# PCB_Project.net
KiCad netlist of a schematic drawn in Altium Designer
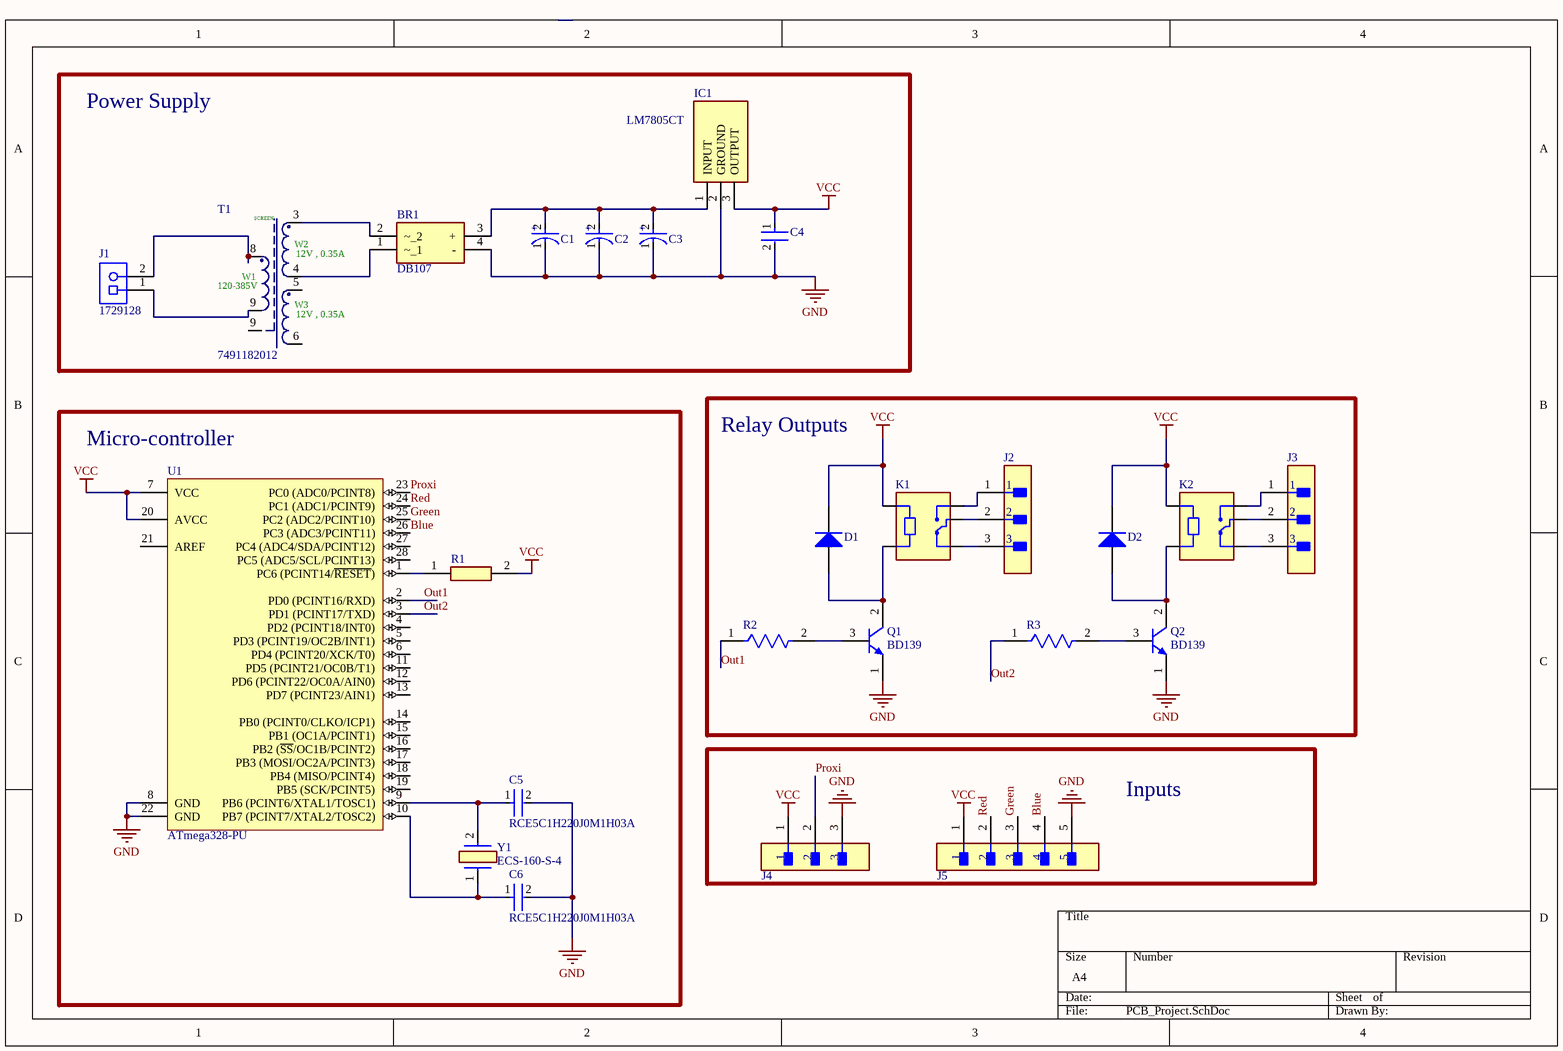
[diagram p0: PCB_Project.SchDoc]

(export (version "E")
  (design (tool "Eeschema 10.0.6"))
  (components
    (comp (ref "BR1")
      (value "DB107")
      (footprint "SamacSys:DIP825W50P510L830H340Q4N")
      (description "Bridge Rectifier")
      (fields (field (name "MOUSER PART NUMBER") "583-DB107"))
      (libsource (lib "*") (part "DB107"))
    )
    (comp (ref "C1")
      (value "EEUTA1E101")
      (footprint "FP-RAD-TH-D_8_0_5-L_11_5-MFG")
      (description "Aluminum Electrolytic Capacitors (Radial Lead Type) AEC-Q200 Qualified 100uF ±20% 25V")
      (fields (field (name "VOLTAGE") "25V") (field (name "TOLERANCE") "20%"))
      (libsource (lib "Altium Content Vault") (part "203bc49f2ac43e59fd269a8c329ed05"))
    )
    (comp (ref "C2")
      (value "ECA2CHG470B")
      (footprint "FP-RAD-TH-D_12_5_0_5-L_20-MFG")
      (description "Aluminum Electrolytic Capacitors (Radial Lead Type) 47uF ±20% 160V")
      (fields (field (name "TOLERANCE") "20%"))
      (libsource (lib "Altium Content Vault") (part "a00bbbee19879c290e62620ae7e47b1"))
    )
    (comp (ref "C3")
      (value "ECA2AM100")
      (footprint "FP-RAD-TH-D_5_0_5-L_11_1-MFG")
      (description "Aluminum Electrolytic Capacitors (Radial Lead Type) 10uF ±20% 100V")
      (fields (field (name "VOLTAGE") "100V") (field (name "TOLERANCE") "20%"))
      (libsource (lib "Altium Content Vault") (part "a00bbbee19879c290e62620ae7e47b1"))
    )
    (comp (ref "C4")
      (value "RCER72A104K1K1H03B")
      (footprint "FP-RCE1K1-2_5-MFG")
      (description "Cap Ceramic Monolithic 100nF 100V 10% Thru-Hole Bulk")
      (fields (field (name "TOLERANCE") "10%"))
      (libsource (lib "Altium Content Vault") (part "02cd4be3c70576c341d710602a673aa"))
    )
    (comp (ref "C5")
      (value "RCE5C1H220J0M1H03A")
      (footprint "FP-RCE0K1-MFG")
      (description "Cap Ceramic 22pF 50V C0G ±5% Radial 5mm +125°C Automotive Bulk")
      (fields (field (name "TOLERANCE") "5%"))
      (libsource (lib "Altium Content Vault") (part "b4654b650e69147ec39a6b967a45e02"))
    )
    (comp (ref "C6")
      (value "RCE5C1H220J0M1H03A")
      (footprint "FP-RCE0K1-MFG")
      (description "Cap Ceramic 22pF 50V C0G ±5% Radial 5mm +125°C Automotive Bulk")
      (fields (field (name "TOLERANCE") "5%"))
      (libsource (lib "Altium Content Vault") (part "b4654b650e69147ec39a6b967a45e02"))
    )
    (comp (ref "D1")
      (value "1N4001-T")
      (footprint "DIOD-DO-41-P-2_V")
      (description "1.0 A Rectifier, 15 pF, 50 V, -65 to 150 degC, 2-Pin DO-41 Plastic, RoHS, Tape and Reel")
      (fields (field (name "MANUFACTURER") "Diodes Inc"))
      (libsource (lib "Altium Content Vault") (part "DIOD-D-A1K2-2"))
    )
    (comp (ref "D2")
      (value "1N4001-T")
      (footprint "DIOD-DO-41-P-2_V")
      (description "1.0 A Rectifier, 15 pF, 50 V, -65 to 150 degC, 2-Pin DO-41 Plastic, RoHS, Tape and Reel")
      (fields (field (name "MANUFACTURER") "Diodes Inc"))
      (libsource (lib "Altium Content Vault") (part "DIOD-D-A1K2-2"))
    )
    (comp (ref "IC1")
      (value "LM7805CT")
      (footprint "SamacSys:TO254P470X1028X1955-3P")
      (description "Integrated Circuit")
      (fields (field (name "MOUSER PART NUMBER") "926-LM7805CT"))
      (libsource (lib "*") (part "LM7805CT"))
    )
    (comp (ref "J1")
      (value "1729128")
      (footprint "PHOE-1729128-2_V")
      (description "PCB Terminal Block, 13.5 A, 400 V, 2-Pin THD, RoHS, Bulk")
      (fields (field (name "MANUFACTURER") "Phoenix Contact"))
      (libsource (lib "Altium Content Vault") (part "CN-2P-F-R2"))
    )
    (comp (ref "J2")
      (value "B3B-XH-A(LF)(SN)")
      (footprint "FP-B3B-XH-A_LF_SN-MFG")
      (description "CONN HEADER VERT 3POS 2.5MM")
      (libsource (lib "Altium Content Vault") (part "0d3f023dd272f625e17a2be33dea85f"))
    )
    (comp (ref "J3")
      (value "B3B-XH-A(LF)(SN)")
      (footprint "FP-B3B-XH-A_LF_SN-MFG")
      (description "CONN HEADER VERT 3POS 2.5MM")
      (libsource (lib "Altium Content Vault") (part "0d3f023dd272f625e17a2be33dea85f"))
    )
    (comp (ref "J4")
      (value "B3B-XH-A(LF)(SN)")
      (footprint "FP-B3B-XH-A_LF_SN-MFG")
      (description "CONN HEADER VERT 3POS 2.5MM")
      (libsource (lib "") (part "0d3f023dd272f625e17a2be33dea85f_1"))
    )
    (comp (ref "J5")
      (value "B5B-EH-A(LF)(SN)")
      (footprint "FP-B5B-EH-A_LF_SN-MFG")
      (description "CONN HEADER VERT 5POS 2.5MM")
      (libsource (lib "Altium Content Vault") (part "bf93c07fd2649a848d0ec8585582aab"))
    )
    (comp (ref "K1")
      (value "SRD-05VDC-SL-C")
      (footprint "RELAY_SRD-05VDC-SL-C")
      (fields (field (name "MF") "Songle Relay"))
      (libsource (lib "SRD-05VDC-SL-C") (part "SRD-05VDC-SL-C"))
    )
    (comp (ref "K2")
      (value "SRD-05VDC-SL-C")
      (footprint "RELAY_SRD-05VDC-SL-C")
      (fields (field (name "MF") "Songle Relay"))
      (libsource (lib "SRD-05VDC-SL-C") (part "SRD-05VDC-SL-C"))
    )
    (comp (ref "Q1")
      (value "BD139")
      (footprint "ONSC-TO-225-3-77-09")
      (description "Plastic Medium-Power Silicon NPN Transistor, 3-Pin TO-225, Bulk Box")
      (fields (field (name "MANUFACTURER") "On Semiconductor"))
      (libsource (lib "Altium Content Vault") (part "ONSC-NPN-E1C2B3-3"))
    )
    (comp (ref "Q2")
      (value "BD139")
      (footprint "ONSC-TO-225-3-77-09")
      (description "Plastic Medium-Power Silicon NPN Transistor, 3-Pin TO-225, Bulk Box")
      (fields (field (name "MANUFACTURER") "On Semiconductor"))
      (libsource (lib "Altium Content Vault") (part "ONSC-NPN-E1C2B3-3"))
    )
    (comp (ref "R1")
      (value "PR02000201001JR500")
      (footprint "SamacSys:RESAD2760W63L1200D390")
      (description "Resistor")
      (fields (field (name "MOUSER PART NUMBER") "594-5083NW1K000J"))
      (libsource (lib "*") (part "PR02000201001JR500"))
    )
    (comp (ref "R2")
      (value "MFR-25FBF52-1K18")
      (footprint "FP-MFR-25-MFG")
      (description "1.18 kOhms ±1% 0.25W, 1/4W Through Hole Resistor Axial  Metal Film")
      (fields (field (name "MANUFACTURER") "Yageo"))
      (libsource (lib "Altium Content Vault") (part "1029c3af85768c4190bb7ad29bc67b5"))
    )
    (comp (ref "R3")
      (value "MFR-25FBF52-1K18")
      (footprint "FP-MFR-25-MFG")
      (description "1.18 kOhms ±1% 0.25W, 1/4W Through Hole Resistor Axial  Metal Film")
      (fields (field (name "MANUFACTURER") "Yageo"))
      (libsource (lib "Altium Content Vault") (part "1029c3af85768c4190bb7ad29bc67b5"))
    )
    (comp (ref "T1")
      (value "7491182012")
      (footprint "EE16_7_4 (E16)")
      (description "Off-Line Transformer WE-UNIT , L=0.9mH")
      (fields (field (name "MANUFACTURER") "Wuerth Elektronik"))
      (libsource (lib "Altium Content Vault") (part "WE-7491182012"))
    )
    (comp (ref "U1")
      (value "ATmega328-PU")
      (footprint "28P3")
      (libsource (lib "Altium Content Vault") (part "MC-8B-ATM48-IL28"))
    )
    (comp (ref "Y1")
      (value "ECS-160-S-4")
      (footprint "SamacSys:ECS160S4")
      (description "Crystal or Oscillator")
      (fields (field (name "MOUSER PART NUMBER") "520-HCU1600-S"))
      (libsource (lib "*") (part "ECS-160-S-4"))
    )
  )
  (nets
    (net (code "1") (name "/Blue") (class "Default")
      (node (ref "J5") (pin "4") (pinfunction "4_4") (pintype "passive"))
      (node (ref "U1") (pin "26") (pinfunction "PC3_(ADC3/PCINT11)_26") (pintype "bidirectional"))
    )
    (net (code "2") (name "/Green") (class "Default")
      (node (ref "J5") (pin "3") (pinfunction "3_3") (pintype "passive"))
      (node (ref "U1") (pin "25") (pinfunction "PC2_(ADC2/PCINT10)_25") (pintype "bidirectional"))
    )
    (net (code "3") (name "/Out1") (class "Default")
      (node (ref "R2") (pin "1") (pinfunction "1_1") (pintype "passive"))
      (node (ref "U1") (pin "2") (pinfunction "PD0_(PCINT16/RXD)_2") (pintype "bidirectional"))
    )
    (net (code "4") (name "/Out2") (class "Default")
      (node (ref "R3") (pin "1") (pinfunction "1_1") (pintype "passive"))
      (node (ref "U1") (pin "3") (pinfunction "PD1_(PCINT17/TXD)_3") (pintype "bidirectional"))
    )
    (net (code "5") (name "/Proxi") (class "Default")
      (node (ref "J4") (pin "2") (pinfunction "2_2") (pintype "passive"))
      (node (ref "U1") (pin "23") (pinfunction "PC0_(ADC0/PCINT8)_23") (pintype "bidirectional"))
    )
    (net (code "6") (name "/Red") (class "Default")
      (node (ref "J5") (pin "2") (pinfunction "2_2") (pintype "passive"))
      (node (ref "U1") (pin "24") (pinfunction "PC1_(ADC1/PCINT9)_24") (pintype "bidirectional"))
    )
    (net (code "7") (name "GND") (class "Default")
      (node (ref "BR1") (pin "4") (pinfunction "-_4") (pintype "passive"))
      (node (ref "C1") (pin "1") (pinfunction "C_1") (pintype "passive"))
      (node (ref "C2") (pin "1") (pinfunction "C_1") (pintype "passive"))
      (node (ref "C3") (pin "1") (pinfunction "C_1") (pintype "passive"))
      (node (ref "C4") (pin "2") (pinfunction "2_2") (pintype "passive"))
      (node (ref "C5") (pin "2") (pinfunction "2_2") (pintype "passive"))
      (node (ref "C6") (pin "2") (pinfunction "2_2") (pintype "passive"))
      (node (ref "IC1") (pin "2") (pinfunction "GROUND_2") (pintype "passive"))
      (node (ref "J4") (pin "3") (pinfunction "3_3") (pintype "passive"))
      (node (ref "J5") (pin "5") (pinfunction "5_5") (pintype "passive"))
      (node (ref "Q1") (pin "1") (pinfunction "E_1") (pintype "passive"))
      (node (ref "Q2") (pin "1") (pinfunction "E_1") (pintype "passive"))
      (node (ref "U1") (pin "22") (pinfunction "GND_22") (pintype "power_in"))
      (node (ref "U1") (pin "8") (pinfunction "GND_8") (pintype "power_in"))
    )
    (net (code "8") (name "Net-(BR1-+)") (class "Default")
      (node (ref "BR1") (pin "3") (pinfunction "+_3") (pintype "passive"))
      (node (ref "C1") (pin "2") (pinfunction "A_2") (pintype "passive"))
      (node (ref "C2") (pin "2") (pinfunction "A_2") (pintype "passive"))
      (node (ref "C3") (pin "2") (pinfunction "A_2") (pintype "passive"))
      (node (ref "IC1") (pin "1") (pinfunction "INPUT_1") (pintype "passive"))
    )
    (net (code "9") (name "Net-(BR1-~_1)") (class "Default")
      (node (ref "BR1") (pin "1") (pinfunction "~_1_1") (pintype "passive"))
      (node (ref "T1") (pin "4") (pinfunction "4_4") (pintype "passive"))
    )
    (net (code "10") (name "Net-(BR1-~_2)") (class "Default")
      (node (ref "BR1") (pin "2") (pinfunction "~_2_2") (pintype "passive"))
      (node (ref "T1") (pin "3") (pinfunction "3_3") (pintype "passive"))
    )
    (net (code "11") (name "Net-(D1-A)") (class "Default")
      (node (ref "D1") (pin "1") (pinfunction "A_1") (pintype "passive"))
      (node (ref "K1") (pin "A2") (pinfunction "A2_A2") (pintype "passive"))
      (node (ref "Q1") (pin "2") (pinfunction "C_2") (pintype "passive"))
    )
    (net (code "12") (name "Net-(D2-A)") (class "Default")
      (node (ref "D2") (pin "1") (pinfunction "A_1") (pintype "passive"))
      (node (ref "K2") (pin "A2") (pinfunction "A2_A2") (pintype "passive"))
      (node (ref "Q2") (pin "2") (pinfunction "C_2") (pintype "passive"))
    )
    (net (code "13") (name "Net-(J1-Pad1)") (class "Default")
      (node (ref "J1") (pin "1") (pinfunction "1_1") (pintype "passive"))
      (node (ref "T1") (pin "9") (pinfunction "9_9") (pintype "passive"))
    )
    (net (code "14") (name "Net-(J1-Pad2)") (class "Default")
      (node (ref "J1") (pin "2") (pinfunction "2_2") (pintype "passive"))
      (node (ref "T1") (pin "8") (pinfunction "8_8") (pintype "passive"))
    )
    (net (code "15") (name "Net-(J2-Pad1)") (class "Default")
      (node (ref "J2") (pin "1") (pinfunction "1_1") (pintype "passive"))
      (node (ref "K1") (pin "NO") (pinfunction "NO_NO") (pintype "passive"))
    )
    (net (code "16") (name "Net-(J2-Pad2)") (class "Default")
      (node (ref "J2") (pin "2") (pinfunction "2_2") (pintype "passive"))
      (node (ref "K1") (pin "COM") (pinfunction "COM_COM") (pintype "passive"))
    )
    (net (code "17") (name "Net-(J2-Pad3)") (class "Default")
      (node (ref "J2") (pin "3") (pinfunction "3_3") (pintype "passive"))
      (node (ref "K1") (pin "NC") (pinfunction "NC_NC") (pintype "passive"))
    )
    (net (code "18") (name "Net-(J3-Pad1)") (class "Default")
      (node (ref "J3") (pin "1") (pinfunction "1_1") (pintype "passive"))
      (node (ref "K2") (pin "NO") (pinfunction "NO_NO") (pintype "passive"))
    )
    (net (code "19") (name "Net-(J3-Pad2)") (class "Default")
      (node (ref "J3") (pin "2") (pinfunction "2_2") (pintype "passive"))
      (node (ref "K2") (pin "COM") (pinfunction "COM_COM") (pintype "passive"))
    )
    (net (code "20") (name "Net-(J3-Pad3)") (class "Default")
      (node (ref "J3") (pin "3") (pinfunction "3_3") (pintype "passive"))
      (node (ref "K2") (pin "NC") (pinfunction "NC_NC") (pintype "passive"))
    )
    (net (code "21") (name "Net-(Q1-B)") (class "Default")
      (node (ref "Q1") (pin "3") (pinfunction "B_3") (pintype "passive"))
      (node (ref "R2") (pin "2") (pinfunction "2_2") (pintype "passive"))
    )
    (net (code "22") (name "Net-(Q2-B)") (class "Default")
      (node (ref "Q2") (pin "3") (pinfunction "B_3") (pintype "passive"))
      (node (ref "R3") (pin "2") (pinfunction "2_2") (pintype "passive"))
    )
    (net (code "23") (name "Net-(U1-PB6_(PCINT6{slash}XTAL1{slash}TOSC1))") (class "Default")
      (node (ref "C5") (pin "1") (pinfunction "1_1") (pintype "passive"))
      (node (ref "U1") (pin "9") (pinfunction "PB6_(PCINT6/XTAL1/TOSC1)_9") (pintype "bidirectional"))
      (node (ref "Y1") (pin "2") (pinfunction "2_2") (pintype "passive"))
    )
    (net (code "24") (name "Net-(U1-PB7_(PCINT7{slash}XTAL2{slash}TOSC2))") (class "Default")
      (node (ref "C6") (pin "1") (pinfunction "1_1") (pintype "passive"))
      (node (ref "U1") (pin "10") (pinfunction "PB7_(PCINT7/XTAL2/TOSC2)_10") (pintype "bidirectional"))
      (node (ref "Y1") (pin "1") (pinfunction "1_1") (pintype "passive"))
    )
    (net (code "25") (name "Net-(U1-PC6_(PCINT14{slash}~{RESET}))") (class "Default")
      (node (ref "R1") (pin "1") (pinfunction "1_1") (pintype "passive"))
      (node (ref "U1") (pin "1") (pinfunction "PC6_(PCINT14/~{RESET})_1") (pintype "bidirectional"))
    )
    (net (code "26") (name "VCC") (class "Default")
      (node (ref "C4") (pin "1") (pinfunction "1_1") (pintype "passive"))
      (node (ref "D1") (pin "2") (pinfunction "K_2") (pintype "passive"))
      (node (ref "D2") (pin "2") (pinfunction "K_2") (pintype "passive"))
      (node (ref "IC1") (pin "3") (pinfunction "OUTPUT_3") (pintype "passive"))
      (node (ref "J4") (pin "1") (pinfunction "1_1") (pintype "passive"))
      (node (ref "J5") (pin "1") (pinfunction "1_1") (pintype "passive"))
      (node (ref "K1") (pin "A1") (pinfunction "A1_A1") (pintype "passive"))
      (node (ref "K2") (pin "A1") (pinfunction "A1_A1") (pintype "passive"))
      (node (ref "R1") (pin "2") (pinfunction "2_2") (pintype "passive"))
      (node (ref "U1") (pin "20") (pinfunction "AVCC_20") (pintype "power_in"))
      (node (ref "U1") (pin "7") (pinfunction "VCC_7") (pintype "power_in"))
    )
    (net (code "27") (name "unconnected-(T1-Pad5)") (class "Default")
      (node (ref "T1") (pin "5") (pinfunction "5_5") (pintype "passive"))
    )
    (net (code "28") (name "unconnected-(T1-Pad6)") (class "Default")
      (node (ref "T1") (pin "6") (pinfunction "6_6") (pintype "passive"))
    )
    (net (code "29") (name "unconnected-(T1-Pad9)") (class "Default")
      (node (ref "T1") (pin "9") (pinfunction "9_9") (pintype "passive"))
    )
    (net (code "30") (name "unconnected-(U1-AREF-Pad21)") (class "Default")
      (node (ref "U1") (pin "21") (pinfunction "AREF_21") (pintype "power_in"))
    )
    (net (code "31") (name "unconnected-(U1-PB0_(PCINT0{slash}CLKO{slash}ICP1)-Pad14)") (class "Default")
      (node (ref "U1") (pin "14") (pinfunction "PB0_(PCINT0/CLKO/ICP1)_14") (pintype "bidirectional"))
    )
    (net (code "32") (name "unconnected-(U1-PB1_(OC1A{slash}PCINT1)-Pad15)") (class "Default")
      (node (ref "U1") (pin "15") (pinfunction "PB1_(OC1A/PCINT1)_15") (pintype "bidirectional"))
    )
    (net (code "33") (name "unconnected-(U1-PB2_(~{SS}{slash}OC1B{slash}PCINT2)-Pad16)") (class "Default")
      (node (ref "U1") (pin "16") (pinfunction "PB2_(~{SS}/OC1B/PCINT2)_16") (pintype "bidirectional"))
    )
    (net (code "34") (name "unconnected-(U1-PB3_(MOSI{slash}OC2A{slash}PCINT3)-Pad17)") (class "Default")
      (node (ref "U1") (pin "17") (pinfunction "PB3_(MOSI/OC2A/PCINT3)_17") (pintype "bidirectional"))
    )
    (net (code "35") (name "unconnected-(U1-PB4_(MISO{slash}PCINT4)-Pad18)") (class "Default")
      (node (ref "U1") (pin "18") (pinfunction "PB4_(MISO/PCINT4)_18") (pintype "bidirectional"))
    )
    (net (code "36") (name "unconnected-(U1-PB5_(SCK{slash}PCINT5)-Pad19)") (class "Default")
      (node (ref "U1") (pin "19") (pinfunction "PB5_(SCK/PCINT5)_19") (pintype "bidirectional"))
    )
    (net (code "37") (name "unconnected-(U1-PC4_(ADC4{slash}SDA{slash}PCINT12)-Pad27)") (class "Default")
      (node (ref "U1") (pin "27") (pinfunction "PC4_(ADC4/SDA/PCINT12)_27") (pintype "bidirectional"))
    )
    (net (code "38") (name "unconnected-(U1-PC5_(ADC5{slash}SCL{slash}PCINT13)-Pad28)") (class "Default")
      (node (ref "U1") (pin "28") (pinfunction "PC5_(ADC5/SCL/PCINT13)_28") (pintype "bidirectional"))
    )
    (net (code "39") (name "unconnected-(U1-PD2_(PCINT18{slash}INT0)-Pad4)") (class "Default")
      (node (ref "U1") (pin "4") (pinfunction "PD2_(PCINT18/INT0)_4") (pintype "bidirectional"))
    )
    (net (code "40") (name "unconnected-(U1-PD3_(PCINT19{slash}OC2B{slash}INT1)-Pad5)") (class "Default")
      (node (ref "U1") (pin "5") (pinfunction "PD3_(PCINT19/OC2B/INT1)_5") (pintype "bidirectional"))
    )
    (net (code "41") (name "unconnected-(U1-PD4_(PCINT20{slash}XCK{slash}T0)-Pad6)") (class "Default")
      (node (ref "U1") (pin "6") (pinfunction "PD4_(PCINT20/XCK/T0)_6") (pintype "bidirectional"))
    )
    (net (code "42") (name "unconnected-(U1-PD5_(PCINT21{slash}OC0B{slash}T1)-Pad11)") (class "Default")
      (node (ref "U1") (pin "11") (pinfunction "PD5_(PCINT21/OC0B/T1)_11") (pintype "bidirectional"))
    )
    (net (code "43") (name "unconnected-(U1-PD6_(PCINT22{slash}OC0A{slash}AIN0)-Pad12)") (class "Default")
      (node (ref "U1") (pin "12") (pinfunction "PD6_(PCINT22/OC0A/AIN0)_12") (pintype "bidirectional"))
    )
    (net (code "44") (name "unconnected-(U1-PD7_(PCINT23{slash}AIN1)-Pad13)") (class "Default")
      (node (ref "U1") (pin "13") (pinfunction "PD7_(PCINT23/AIN1)_13") (pintype "bidirectional"))
    )
  )
)
